# Accel.net
KiCad netlist of a schematic drawn in Altium Designer
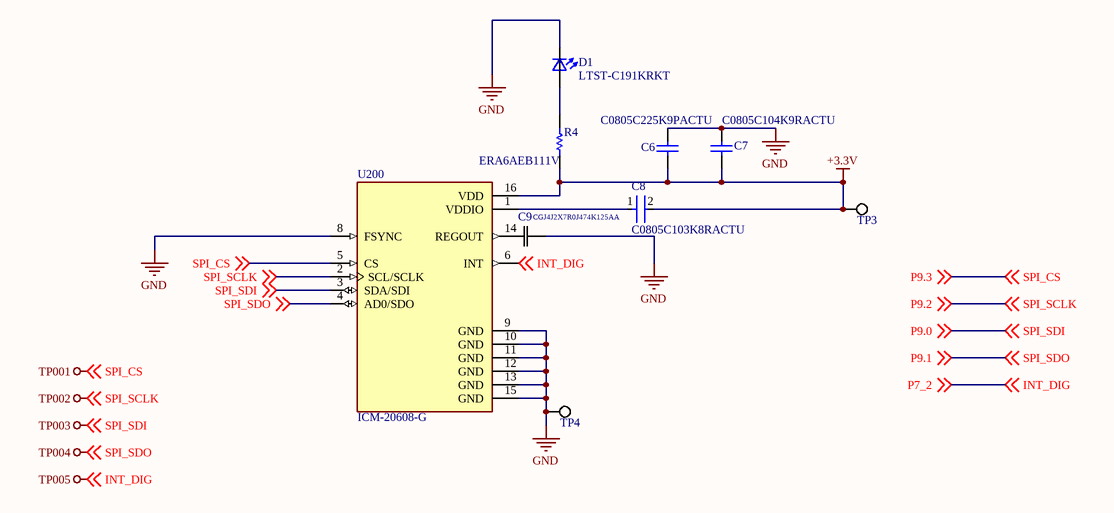
[diagram p0: Accel.SchDoc]

(export (version "E")
  (design (tool "Eeschema 10.0.6"))
  (components
    (comp (ref "C6")
      (value "C0805C225K9PACTU")
      (footprint "CAPC2013X145X50ML20T25")
      (fields (field (name "MANUFACTURER") "Kemet"))
      (libsource (lib "Altium Content Vault") (part "CAP"))
    )
    (comp (ref "C7")
      (value "C0805C104K9RACTU")
      (footprint "CAPC2013X145X50LL20T25")
      (fields (field (name "MANUFACTURER") "Kemet"))
      (libsource (lib "Altium Content Vault") (part "CAP"))
    )
    (comp (ref "C8")
      (value "C0805C103K8RACTU")
      (footprint "FP-C0805C-DN-MFG")
      (description "CAP CER 10000PF 10V X7R 0805")
      (fields
        (field (name "OCTOPART") "https://octopart.com/c0805c103k8ractu-kemet-12595572")
        (field (name "MANUFACTURER") "KEMET")
      )
      (libsource (lib "Altium Content Vault") (part "b4654b650e69147ec39a6b967a45e02"))
    )
    (comp (ref "C9")
      (value "CGJ4J2X7R0J474K125AA")
      (footprint "CAP_2012_TDK")
      (description "No Description Available")
      (libsource (lib "CGJ4J2X7R0J474K125AA") (part "CGJ4J2X7R0J474K125AA"))
    )
    (comp (ref "D1")
      (value "LTST-C191KRKT")
      (footprint "0603:0603")
      (description "http://octopart.com/ltst-c190krkt-lite-on-549893")
      (libsource (lib "LTST-C191KRKT") (part "LTST-C191KRKT"))
    )
    (comp (ref "R4")
      (value "ERA6AEB111V")
      (footprint "RESC2013X60X40NL20T25")
      (fields (field (name "MANUFACTURER") "Panasonic"))
      (libsource (lib "Altium Content Vault") (part "RES"))
    )
    (comp (ref "TP3")
      (value "5019")
      (footprint "KSTN-5019_V")
      (description "Test Point, 1 Position SMD, RoHS, Tape and Reel")
      (libsource (lib "Altium Content Vault") (part "TESTPOINT_WHITE"))
    )
    (comp (ref "TP4")
      (value "5019")
      (footprint "KSTN-5019_V")
      (description "Test Point, 1 Position SMD, RoHS, Tape and Reel")
      (libsource (lib "Altium Content Vault") (part "TESTPOINT_WHITE"))
    )
    (comp (ref "U200")
      (value "ICM-20608-G")
      (footprint "PQFN50P300X300X80-16N")
      (description "Accelerometer, Gyroscope, 6 Axis Sensor IÂ²C, SPI Output")
      (fields (field (name "MF") "TDK InvenSense"))
      (libsource (lib "ICM-20608-G") (part "ICM-20608-G"))
    )
  )
  (nets
    (net (code "1") (name "+3.3V") (class "Default")
      (node (ref "C6") (pin "1") (pinfunction "1_1") (pintype "passive"))
      (node (ref "C7") (pin "1") (pinfunction "1_1") (pintype "passive"))
      (node (ref "C8") (pin "2") (pinfunction "2_2") (pintype "passive"))
      (node (ref "R4") (pin "1") (pinfunction "1_1") (pintype "passive"))
      (node (ref "TP3") (pin "1") (pinfunction "1_1") (pintype "passive"))
      (node (ref "U200") (pin "16") (pinfunction "VDD_16") (pintype "power_in"))
    )
    (net (code "2") (name "GND") (class "Default")
      (node (ref "C6") (pin "2") (pinfunction "2_2") (pintype "passive"))
      (node (ref "C7") (pin "2") (pinfunction "2_2") (pintype "passive"))
      (node (ref "C9") (pin "2") (pinfunction "2_2") (pintype "passive"))
      (node (ref "D1") (pin "1") (pinfunction "K2_1") (pintype "passive"))
      (node (ref "TP4") (pin "1") (pinfunction "1_1") (pintype "passive"))
      (node (ref "U200") (pin "10") (pinfunction "GND_10") (pintype "power_in"))
      (node (ref "U200") (pin "11") (pinfunction "GND_11") (pintype "power_in"))
      (node (ref "U200") (pin "12") (pinfunction "GND_12") (pintype "power_in"))
      (node (ref "U200") (pin "13") (pinfunction "GND_13") (pintype "power_in"))
      (node (ref "U200") (pin "15") (pinfunction "GND_15") (pintype "power_in"))
      (node (ref "U200") (pin "8") (pinfunction "FSYNC_8") (pintype "input"))
      (node (ref "U200") (pin "9") (pinfunction "GND_9") (pintype "power_in"))
    )
    (net (code "3") (name "INT_DIG") (class "Default")
      (node (ref "U200") (pin "6") (pinfunction "INT_6") (pintype "output"))
    )
    (net (code "4") (name "Net-(D1-A2)") (class "Default")
      (node (ref "D1") (pin "2") (pinfunction "A2_2") (pintype "passive"))
      (node (ref "R4") (pin "2") (pinfunction "2_2") (pintype "passive"))
    )
    (net (code "5") (name "Net-(U200-VDDIO)") (class "Default")
      (node (ref "C8") (pin "1") (pinfunction "1_1") (pintype "passive"))
      (node (ref "U200") (pin "1") (pinfunction "VDDIO_1") (pintype "power_in"))
    )
    (net (code "6") (name "P9.0") (class "Default")
      (node (ref "U200") (pin "3") (pinfunction "SDA/SDI_3") (pintype "bidirectional"))
    )
    (net (code "7") (name "P9.1") (class "Default")
      (node (ref "U200") (pin "4") (pinfunction "AD0/SDO_4") (pintype "bidirectional"))
    )
    (net (code "8") (name "P9.2") (class "Default")
      (node (ref "U200") (pin "2") (pinfunction "SCL/SCLK_2") (pintype "input"))
    )
    (net (code "9") (name "P9.3") (class "Default")
      (node (ref "U200") (pin "5") (pinfunction "CS_5") (pintype "input"))
    )
    (net (code "10") (name "unconnected-(C9-Pad1)") (class "Default")
      (node (ref "C9") (pin "1") (pinfunction "1_1") (pintype "passive"))
    )
    (net (code "11") (name "unconnected-(U200-REGOUT-Pad14)") (class "Default")
      (node (ref "U200") (pin "14") (pinfunction "REGOUT_14") (pintype "output"))
    )
  )
)
